# Sheet1.net
KiCad netlist of a schematic drawn in Altium Designer
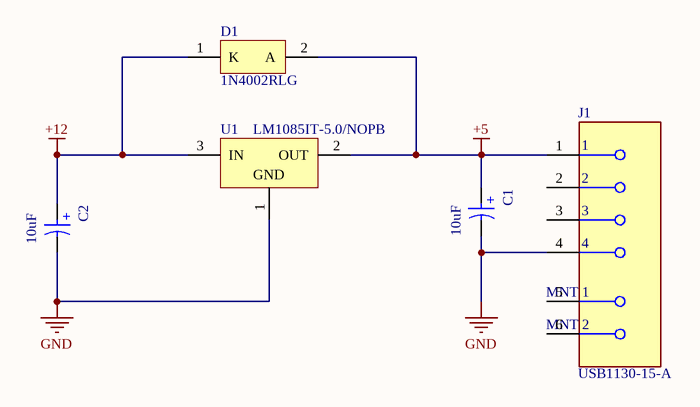
[diagram p0: Sheet1.SchDoc]

(export (version "E")
  (design (tool "Eeschema 10.0.6"))
  (components
    (comp (ref "C1")
      (value "10uF")
      (footprint "WCAP-ASLI_D4H5.5")
      (description "WCAP-ASLI Aluminum Electrolytic Capacitors")
      (fields (field (name "TOLERANCE") "20%"))
      (libsource (lib "Altium Content Vault") (part "Capacitor_Polarized"))
    )
    (comp (ref "C2")
      (value "10uF")
      (footprint "WCAP-ASLI_D4H5.5")
      (description "WCAP-ASLI Aluminum Electrolytic Capacitors")
      (fields (field (name "TOLERANCE") "20%"))
      (libsource (lib "Altium Content Vault") (part "Capacitor_Polarized"))
    )
    (comp (ref "D1")
      (value "1N4002RLG")
      (footprint "ONSC-AXIAL_LEAD-2-59-10_P")
      (description "Standard Recovery Rectifier, 2-Pin Axial_Lead, Pb-Free, Tape and Reel")
      (fields (field (name "MANUFACTURER") "On Semiconductor"))
      (libsource (lib "Altium Content Vault") (part "ONSC-D-K1A2-2_A"))
    )
    (comp (ref "J1")
      (value "USB1130-15-A")
      (footprint "FP-USB1130-15-A-MFG")
      (description "USB1130-15-A USB Connectors USB A 2.0 Skt RA High Life 15u T Hole W/Shell Stake T & R")
      (libsource (lib "Altium Content Vault") (part "79e6714efa0bb2f851c24b2688127c9"))
    )
    (comp (ref "U1")
      (value "LM1085IT-5.0/NOPB")
      (footprint "NDE0003A")
      (description "3A Low Dropout Positive Regulators, 3-pin TO-220, Pb-Free")
      (fields (field (name "MANUFACTURER") "Texas Instruments"))
      (libsource (lib "Altium Content Vault") (part "PM-REG-LM1086-SIL3"))
    )
  )
  (nets
    (net (code "1") (name "+5") (class "Default")
      (node (ref "C1") (pin "1") (pinfunction "P_1") (pintype "passive"))
      (node (ref "D1") (pin "2") (pinfunction "A_2") (pintype "passive"))
      (node (ref "J1") (pin "1") (pinfunction "1_1") (pintype "passive"))
      (node (ref "U1") (pin "2") (pinfunction "OUT_2") (pintype "power_in"))
    )
    (net (code "2") (name "+12") (class "Default")
      (node (ref "C2") (pin "1") (pinfunction "P_1") (pintype "passive"))
      (node (ref "D1") (pin "1") (pinfunction "K_1") (pintype "passive"))
      (node (ref "U1") (pin "3") (pinfunction "IN_3") (pintype "power_in"))
    )
    (net (code "3") (name "GND") (class "Default")
      (node (ref "C1") (pin "2") (pinfunction "N_2") (pintype "passive"))
      (node (ref "C2") (pin "2") (pinfunction "N_2") (pintype "passive"))
      (node (ref "J1") (pin "4") (pinfunction "4_4") (pintype "passive"))
      (node (ref "U1") (pin "1") (pinfunction "GND_1") (pintype "power_in"))
    )
    (net (code "4") (name "unconnected-(J1-MNT_1-Pad5)") (class "Default")
      (node (ref "J1") (pin "5") (pinfunction "MNT_1_5") (pintype "passive"))
    )
    (net (code "5") (name "unconnected-(J1-MNT_2-Pad6)") (class "Default")
      (node (ref "J1") (pin "6") (pinfunction "MNT_2_6") (pintype "passive"))
    )
    (net (code "6") (name "unconnected-(J1-Pad2)") (class "Default")
      (node (ref "J1") (pin "2") (pinfunction "2_2") (pintype "passive"))
    )
    (net (code "7") (name "unconnected-(J1-Pad3)") (class "Default")
      (node (ref "J1") (pin "3") (pinfunction "3_3") (pintype "passive"))
    )
  )
)
